# Power_and_Shield_Conn.net
KiCad netlist of a schematic drawn in Altium Designer
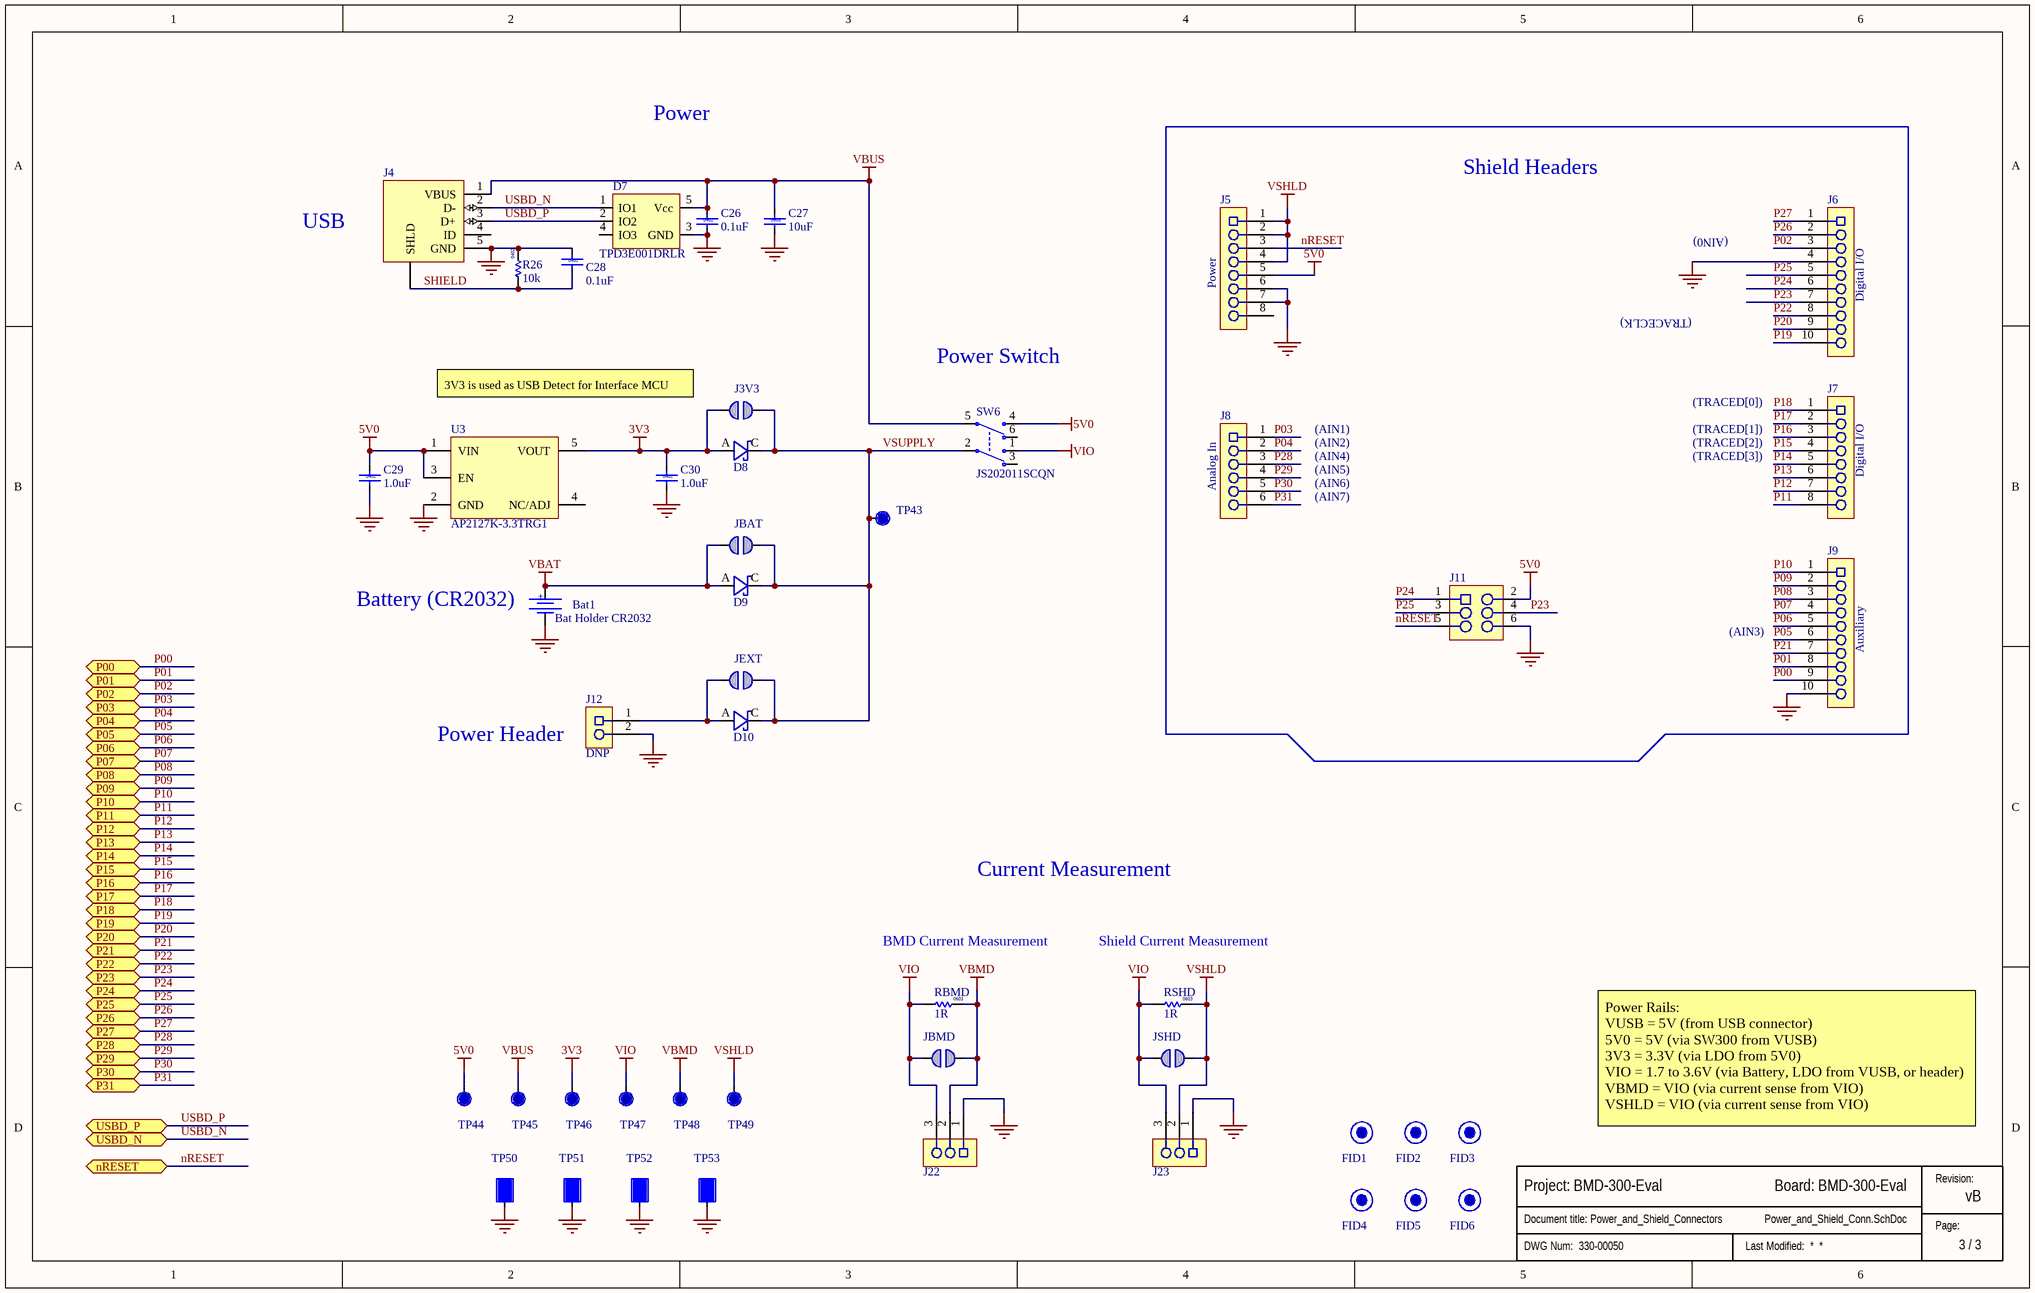
[diagram p0: Power_and_Shield_Conn.SchDoc]

(export (version "E")
  (design (tool "Eeschema 10.0.6"))
  (components
    (comp (ref "Bat1")
      (value "Bat Holder CR2032")
      (footprint "CR2032_HOLDER_SMD")
      (description "Bat Holder CR2032 SMD")
      (fields
        (field (name "MANUFACTURER") "Keystone")
        (field (name "MANUFACTURER PART NUMBER") "3002")
        (field (name "PUBLISHER") "Nordic Semiconductor")
      )
      (libsource (lib "pca10036") (part "Battery"))
    )
    (comp (ref "C26")
      (value "0.1uF")
      (footprint "Cap 0402 HD")
      (description "Cap, Ceramic 0.1uF 10V 10% X5R 0402")
      (fields
        (field (name "SIZE") "0402")
        (field (name "PART NUMBER") "120-00016")
        (field (name "MANUFACTURER") "Murata Electronics North America")
      )
      (libsource (lib "Arena-Altium DB") (part "Cap Chip"))
    )
    (comp (ref "C27")
      (value "10uF")
      (footprint "Cap 0603 HD")
      (description "Cap, Ceramic 10uF 10V 20% X5R 0603")
      (fields
        (field (name "SIZE") "0603")
        (field (name "PART NUMBER") "120-00024")
        (field (name "MANUFACTURER") "Murata Electronics North America")
      )
      (libsource (lib "Arena-Altium DB") (part "Cap Chip"))
    )
    (comp (ref "C28")
      (value "0.1uF")
      (footprint "Cap 0402 HD")
      (description "Cap, Ceramic 0.1uF 10V 10% X5R 0402")
      (fields
        (field (name "SIZE") "0402")
        (field (name "PART NUMBER") "120-00016")
        (field (name "MANUFACTURER") "Murata Electronics North America")
      )
      (libsource (lib "Arena-Altium DB") (part "Cap Chip"))
    )
    (comp (ref "C29")
      (value "1.0uF")
      (footprint "Cap 0402 HD")
      (description "Cap, Ceramic, 1.0uF 10V 10% X5R, 0402")
      (fields
        (field (name "SIZE") "0402")
        (field (name "PART NUMBER") "120-00017")
        (field (name "MANUFACTURER") "Murata Electronics North America")
      )
      (libsource (lib "Arena-Altium DB") (part "Cap Chip"))
    )
    (comp (ref "C30")
      (value "1.0uF")
      (footprint "Cap 0402 HD")
      (description "Cap, Ceramic, 1.0uF 10V 10% X5R, 0402")
      (fields
        (field (name "SIZE") "0402")
        (field (name "PART NUMBER") "120-00017")
        (field (name "MANUFACTURER") "Murata Electronics North America")
      )
      (libsource (lib "Arena-Altium DB") (part "Cap Chip"))
    )
    (comp (ref "D7")
      (value "110-00018")
      (footprint "SOT-553")
      (description "LOW-CAPACITANCE 3-CHANNEL ESD-PROTECTION ARRAY")
      (fields
        (field (name "MANUFACTURER P/N") "TPD3E001DRLR")
        (field (name "MANUFACTURER") "Texas Instruments")
        (field (name "VOLTAGE") "5V")
      )
      (libsource (lib "Arena-Altium DB") (part "TPD3E001"))
    )
    (comp (ref "D8")
      (value "110-00008")
      (footprint "SOD-123")
      (fields (field (name "MANUFACTURER") "Fairchild Semiconductor") (field (name "VOLTAGE") "20V"))
      (libsource (lib "Arena-Altium DB") (part "Diode_Schottky"))
    )
    (comp (ref "D9")
      (value "110-00008")
      (footprint "SOD-123")
      (fields (field (name "MANUFACTURER") "Fairchild Semiconductor") (field (name "VOLTAGE") "20V"))
      (libsource (lib "Arena-Altium DB") (part "Diode_Schottky"))
    )
    (comp (ref "D10")
      (value "110-00008")
      (footprint "SOD-123")
      (fields (field (name "MANUFACTURER") "Fairchild Semiconductor") (field (name "VOLTAGE") "20V"))
      (libsource (lib "Arena-Altium DB") (part "Diode_Schottky"))
    )
    (comp (ref "FID1")
      (value "FID")
      (footprint "FIDUCIAL40")
      (description "Fiducial, 0.040\" inner Dia, 0.075\" outer Dia")
      (fields
        (field (name "PART NUMBER") "FIDUCIAL.04")
        (field (name "ADDED BY") "Jeremy D")
        (field (name "CHECKED BY") "Paul B")
      )
      (libsource (lib "LEGACY_Rigado_AltiumLib") (part "FIDUCIAL"))
    )
    (comp (ref "FID2")
      (value "FID")
      (footprint "FIDUCIAL40")
      (description "Fiducial, 0.040\" inner Dia, 0.075\" outer Dia")
      (fields
        (field (name "PART NUMBER") "FIDUCIAL.04")
        (field (name "ADDED BY") "Jeremy D")
        (field (name "CHECKED BY") "Paul B")
      )
      (libsource (lib "LEGACY_Rigado_AltiumLib") (part "FIDUCIAL"))
    )
    (comp (ref "FID3")
      (value "FID")
      (footprint "FIDUCIAL40")
      (description "Fiducial, 0.040\" inner Dia, 0.075\" outer Dia")
      (fields
        (field (name "PART NUMBER") "FIDUCIAL.04")
        (field (name "ADDED BY") "Jeremy D")
        (field (name "CHECKED BY") "Paul B")
      )
      (libsource (lib "LEGACY_Rigado_AltiumLib") (part "FIDUCIAL"))
    )
    (comp (ref "FID4")
      (value "FID")
      (footprint "FIDUCIAL40")
      (description "Fiducial, 0.040\" inner Dia, 0.075\" outer Dia")
      (fields
        (field (name "PART NUMBER") "FIDUCIAL.04")
        (field (name "ADDED BY") "Jeremy D")
        (field (name "CHECKED BY") "Paul B")
      )
      (libsource (lib "LEGACY_Rigado_AltiumLib") (part "FIDUCIAL"))
    )
    (comp (ref "FID5")
      (value "FID")
      (footprint "FIDUCIAL40")
      (description "Fiducial, 0.040\" inner Dia, 0.075\" outer Dia")
      (fields
        (field (name "PART NUMBER") "FIDUCIAL.04")
        (field (name "ADDED BY") "Jeremy D")
        (field (name "CHECKED BY") "Paul B")
      )
      (libsource (lib "LEGACY_Rigado_AltiumLib") (part "FIDUCIAL"))
    )
    (comp (ref "FID6")
      (value "FID")
      (footprint "FIDUCIAL40")
      (description "Fiducial, 0.040\" inner Dia, 0.075\" outer Dia")
      (fields
        (field (name "PART NUMBER") "FIDUCIAL.04")
        (field (name "ADDED BY") "Jeremy D")
        (field (name "CHECKED BY") "Paul B")
      )
      (libsource (lib "LEGACY_Rigado_AltiumLib") (part "FIDUCIAL"))
    )
    (comp (ref "J3V3")
      (value "Solderbridge-OpenDNP")
      (footprint "Solderbridge-Open")
      (description "Solderbridge-Open")
      (fields (field (name "ADDED BY") "Paul B"))
      (libsource (lib "LEGACY_Rigado_AltiumLib") (part "Solderbridge-Open"))
    )
    (comp (ref "J4")
      (value "130-00008")
      (footprint "USB_Micro_RA_W-2TABS")
      (description "USB Micro B Receptacle, Right Angle, SMT with 2 TH Tabs")
      (fields (field (name "MANUFACTURER") "FCI"))
      (libsource (lib "Arena-Altium DB") (part "USB_W-Shield"))
    )
    (comp (ref "J5")
      (value "130-00102")
      (footprint "SKT-0.1P-SSM-108-L-SV")
      (description "Con Socket Strip 0.1\" 8 Pin 1Row SMD")
      (fields (field (name "MANUFACTURER") "Samtec") (field (name "VOLTAGE") "572VDC"))
      (libsource (lib "") (part "CON-8Pin_1Row_1"))
    )
    (comp (ref "J6")
      (value "130-00101")
      (footprint "SKT-0.1P-SSM-110-L-SV")
      (description "Con Socket Strip 0.1\" 10Pin 1Row SMD")
      (fields (field (name "MANUFACTURER") "Samtec") (field (name "VOLTAGE") "572VDC"))
      (libsource (lib "Arena-Altium DB") (part "CON-10Pin_1Row"))
    )
    (comp (ref "J7")
      (value "130-00102")
      (footprint "SKT-0.1P-SSM-108-L-SV")
      (description "Con Socket Strip 0.1\" 8 Pin 1Row SMD")
      (fields (field (name "MANUFACTURER") "Samtec") (field (name "VOLTAGE") "572VDC"))
      (libsource (lib "Arena-Altium DB") (part "CON-8Pin_1Row"))
    )
    (comp (ref "J8")
      (value "130-00103")
      (footprint "SKT-0.1P-SSM-106-L-SV")
      (description "Con Socket Strip 0.1\" 6Pin 1Row SMD")
      (fields (field (name "MANUFACTURER") "Samtec") (field (name "VOLTAGE") "572VDC"))
      (libsource (lib "Arena-Altium DB") (part "CON-6Pin_1Row"))
    )
    (comp (ref "J9")
      (value "130-00101")
      (footprint "SKT-0.1P-SSM-110-L-SV")
      (description "Con Socket Strip 0.1\" 10Pin 1Row SMD")
      (fields (field (name "MANUFACTURER") "Samtec") (field (name "VOLTAGE") "572VDC"))
      (libsource (lib "Arena-Altium DB") (part "CON-10Pin_1Row"))
    )
    (comp (ref "J11")
      (value "130-00104")
      (footprint "HDR-0.1P-6Pin-3x2-SMT")
      (description "Header 0.1\" 6 Pin 2 Row SMD Black")
      (fields (field (name "MANUFACTURER") "Molex Inc"))
      (libsource (lib "Arena-Altium DB") (part "CON-6Pin_2Row"))
    )
    (comp (ref "J12")
      (value "130-00048DNP")
      (footprint "HDR-0.1P-2PIN-TH")
      (description "Header 0.100\" Pitch, 2 Pin, 2x1, TH.")
      (fields
        (field (name "DNP") "DNP")
        (field (name "PART NUMBER") "130-00048")
        (field (name "MANUFACTURER") "Sullins Connector Solutions")
      )
      (libsource (lib "Arena-Altium DB") (part "CON-2Pin_1Row"))
    )
    (comp (ref "J22")
      (value "130-00105")
      (footprint "HDR-0.1P-3Pin-1Row-SMT")
      (description "Header, 0.100\" Pitch, 3 Pin, Vertical SMT")
      (fields (field (name "MANUFACTURER") "Harwin Inc"))
      (libsource (lib "Arena-Altium DB") (part "CON-3Pin_1Row"))
    )
    (comp (ref "J23")
      (value "130-00105")
      (footprint "HDR-0.1P-3Pin-1Row-SMT")
      (description "Header, 0.100\" Pitch, 3 Pin, Vertical SMT")
      (fields (field (name "MANUFACTURER") "Harwin Inc"))
      (libsource (lib "Arena-Altium DB") (part "CON-3Pin_1Row"))
    )
    (comp (ref "JBAT")
      (value "Solderbridge-OpenDNP")
      (footprint "Solderbridge-Open")
      (description "Solderbridge-Open")
      (fields (field (name "ADDED BY") "Paul B"))
      (libsource (lib "LEGACY_Rigado_AltiumLib") (part "Solderbridge-Open"))
    )
    (comp (ref "JBMD")
      (value "Solderbridge-OpenDNP")
      (footprint "Solderbridge-Open")
      (description "Solderbridge-Open")
      (fields (field (name "ADDED BY") "Paul B"))
      (libsource (lib "LEGACY_Rigado_AltiumLib") (part "Solderbridge-Open"))
    )
    (comp (ref "JEXT")
      (value "Solderbridge-OpenDNP")
      (footprint "Solderbridge-Open")
      (description "Solderbridge-Open")
      (fields (field (name "ADDED BY") "Paul B"))
      (libsource (lib "LEGACY_Rigado_AltiumLib") (part "Solderbridge-Open"))
    )
    (comp (ref "JSHD")
      (value "Solderbridge-OpenDNP")
      (footprint "Solderbridge-Open")
      (description "Solderbridge-Open")
      (fields (field (name "ADDED BY") "Paul B"))
      (libsource (lib "LEGACY_Rigado_AltiumLib") (part "Solderbridge-Open"))
    )
    (comp (ref "R26")
      (value "10k")
      (footprint "RES 0402 HD")
      (description "Resistor 10k ohm 1% 1/16W, 0402")
      (fields
        (field (name "SIZE") "0402")
        (field (name "PART NUMBER") "180-00024")
        (field (name "MANUFACTURER") "Rohm Semiconductor")
      )
      (libsource (lib "Arena-Altium DB") (part "Res sm"))
    )
    (comp (ref "RBMD")
      (value "1R")
      (footprint "RES 0603 HD")
      (description "Resistor 1 ohm 1%, 1/10W, 0603")
      (fields
        (field (name "SIZE") "0603")
        (field (name "PART NUMBER") "180-00109")
        (field (name "MANUFACTURER") "Samsung Electro-Mechanics America, Inc")
      )
      (libsource (lib "Arena-Altium DB") (part "Res sm"))
    )
    (comp (ref "RSHD")
      (value "1R")
      (footprint "RES 0603 HD")
      (description "Resistor 1 ohm 1%, 1/10W, 0603")
      (fields
        (field (name "SIZE") "0603")
        (field (name "PART NUMBER") "180-00109")
        (field (name "MANUFACTURER") "Samsung Electro-Mechanics America, Inc")
      )
      (libsource (lib "Arena-Altium DB") (part "Res sm"))
    )
    (comp (ref "SW6")
      (value "137-00006")
      (footprint "SW_Slide_DPDT_JS202011SCQN")
      (description "SWITCH SLIDE DPDT 300MA 6V SMD")
      (fields
        (field (name "MANUFACTURER P/N") "JS202011SCQN")
        (field (name "MANUFACTURER") "C&K Components")
        (field (name "VOLTAGE") "6V")
      )
      (libsource (lib "Arena-Altium DB") (part "SW_DPDT"))
    )
    (comp (ref "TP43")
      (value "TP")
      (footprint "TP10R")
      (description "Testpoint, Round 1.0mm Dia")
      (fields
        (field (name "PART NUMBER") "TP10R")
        (field (name "ADDED BY") "Jeremy D")
        (field (name "CHECKED BY") "Paul B")
      )
      (libsource (lib "LEGACY_Rigado_AltiumLib") (part "TP_R"))
    )
    (comp (ref "TP44")
      (value "TP")
      (footprint "TP12R")
      (description "Testpoint, Round 1.2mm Dia")
      (fields (field (name "PART NUMBER") "TP12R") (field (name "ADDED BY") "Cam N"))
      (libsource (lib "LEGACY_Rigado_AltiumLib") (part "TP_R"))
    )
    (comp (ref "TP45")
      (value "TP")
      (footprint "TP12R")
      (description "Testpoint, Round 1.2mm Dia")
      (fields (field (name "PART NUMBER") "TP12R") (field (name "ADDED BY") "Cam N"))
      (libsource (lib "LEGACY_Rigado_AltiumLib") (part "TP_R"))
    )
    (comp (ref "TP46")
      (value "TP")
      (footprint "TP12R")
      (description "Testpoint, Round 1.2mm Dia")
      (fields (field (name "PART NUMBER") "TP12R") (field (name "ADDED BY") "Cam N"))
      (libsource (lib "LEGACY_Rigado_AltiumLib") (part "TP_R"))
    )
    (comp (ref "TP47")
      (value "TP")
      (footprint "TP12R")
      (description "Testpoint, Round 1.2mm Dia")
      (fields (field (name "PART NUMBER") "TP12R") (field (name "ADDED BY") "Cam N"))
      (libsource (lib "LEGACY_Rigado_AltiumLib") (part "TP_R"))
    )
    (comp (ref "TP48")
      (value "TP")
      (footprint "TP12R")
      (description "Testpoint, Round 1.2mm Dia")
      (fields (field (name "PART NUMBER") "TP12R") (field (name "ADDED BY") "Cam N"))
      (libsource (lib "LEGACY_Rigado_AltiumLib") (part "TP_R"))
    )
    (comp (ref "TP49")
      (value "TP")
      (footprint "TP12R")
      (description "Testpoint, Round 1.2mm Dia")
      (fields (field (name "PART NUMBER") "TP12R") (field (name "ADDED BY") "Cam N"))
      (libsource (lib "LEGACY_Rigado_AltiumLib") (part "TP_R"))
    )
    (comp (ref "TP50")
      (value "TP4.5x3SqDNP")
      (footprint "TP4.5x3Sq")
      (description "Testpoint, Rectangular 4.5mm x 3mm")
      (fields (field (name "PART NUMBER") "TP4.5x3Sq") (field (name "ADDED BY") "Jeremy D"))
      (libsource (lib "LEGACY_Rigado_AltiumLib") (part "TP_Sq"))
    )
    (comp (ref "TP51")
      (value "TP4.5x3SqDNP")
      (footprint "TP4.5x3Sq")
      (description "Testpoint, Rectangular 4.5mm x 3mm")
      (fields (field (name "PART NUMBER") "TP4.5x3Sq") (field (name "ADDED BY") "Jeremy D"))
      (libsource (lib "LEGACY_Rigado_AltiumLib") (part "TP_Sq"))
    )
    (comp (ref "TP52")
      (value "TP4.5x3SqDNP")
      (footprint "TP4.5x3Sq")
      (description "Testpoint, Rectangular 4.5mm x 3mm")
      (fields (field (name "PART NUMBER") "TP4.5x3Sq") (field (name "ADDED BY") "Jeremy D"))
      (libsource (lib "LEGACY_Rigado_AltiumLib") (part "TP_Sq"))
    )
    (comp (ref "TP53")
      (value "TP4.5x3SqDNP")
      (footprint "TP4.5x3Sq")
      (description "Testpoint, Rectangular 4.5mm x 3mm")
      (fields (field (name "PART NUMBER") "TP4.5x3Sq") (field (name "ADDED BY") "Jeremy D"))
      (libsource (lib "LEGACY_Rigado_AltiumLib") (part "TP_Sq"))
    )
    (comp (ref "U3")
      (value "260-00024")
      (footprint "SOT-23-5")
      (description "IC REG LDO 3.3V 0.3A SOT23-5")
      (fields
        (field (name "MANUFACTURER P/N") "AP2127K-3.3TRG1")
        (field (name "MANUFACTURER") "Diodes Incorporated")
        (field (name "VOLTAGE") "6V")
      )
      (libsource (lib "Arena-Altium DB") (part "LDO_5Pin_ALT"))
    )
  )
  (nets
    (net (code "1") (name "/P00") (class "Default") (node (ref "J9") (pin "9") (pintype "passive")))
    (net (code "2") (name "/P01") (class "Default") (node (ref "J9") (pin "8") (pintype "passive")))
    (net (code "3") (name "/P02") (class "Default") (node (ref "J6") (pin "3") (pintype "passive")))
    (net (code "4") (name "/P03") (class "Default")
      (node (ref "J8") (pin "1") (pinfunction "1_1") (pintype "passive"))
    )
    (net (code "5") (name "/P04") (class "Default")
      (node (ref "J8") (pin "2") (pinfunction "2_2") (pintype "passive"))
    )
    (net (code "6") (name "/P05") (class "Default") (node (ref "J9") (pin "6") (pintype "passive")))
    (net (code "7") (name "/P06") (class "Default") (node (ref "J9") (pin "5") (pintype "passive")))
    (net (code "8") (name "/P07") (class "Default") (node (ref "J9") (pin "4") (pintype "passive")))
    (net (code "9") (name "/P08") (class "Default") (node (ref "J9") (pin "3") (pintype "passive")))
    (net (code "10") (name "/P09") (class "Default") (node (ref "J9") (pin "2") (pintype "passive")))
    (net (code "11") (name "/P10") (class "Default") (node (ref "J9") (pin "1") (pintype "passive")))
    (net (code "12") (name "/P11") (class "Default") (node (ref "J7") (pin "8") (pintype "passive")))
    (net (code "13") (name "/P12") (class "Default") (node (ref "J7") (pin "7") (pintype "passive")))
    (net (code "14") (name "/P13") (class "Default") (node (ref "J7") (pin "6") (pintype "passive")))
    (net (code "15") (name "/P14") (class "Default") (node (ref "J7") (pin "5") (pintype "passive")))
    (net (code "16") (name "/P15") (class "Default") (node (ref "J7") (pin "4") (pintype "passive")))
    (net (code "17") (name "/P16") (class "Default") (node (ref "J7") (pin "3") (pintype "passive")))
    (net (code "18") (name "/P17") (class "Default") (node (ref "J7") (pin "2") (pintype "passive")))
    (net (code "19") (name "/P18") (class "Default") (node (ref "J7") (pin "1") (pintype "passive")))
    (net (code "20") (name "/P19") (class "Default") (node (ref "J6") (pin "10") (pintype "passive")))
    (net (code "21") (name "/P20") (class "Default") (node (ref "J6") (pin "9") (pintype "passive")))
    (net (code "22") (name "/P21") (class "Default") (node (ref "J9") (pin "7") (pintype "passive")))
    (net (code "23") (name "/P22") (class "Default") (node (ref "J6") (pin "8") (pintype "passive")))
    (net (code "24") (name "/P23") (class "Default")
      (node (ref "J11") (pin "4") (pintype "passive"))
      (node (ref "J6") (pin "7") (pintype "passive"))
    )
    (net (code "25") (name "/P24") (class "Default")
      (node (ref "J11") (pin "1") (pintype "passive"))
      (node (ref "J6") (pin "6") (pintype "passive"))
    )
    (net (code "26") (name "/P25") (class "Default")
      (node (ref "J11") (pin "3") (pintype "passive"))
      (node (ref "J6") (pin "5") (pintype "passive"))
    )
    (net (code "27") (name "/P26") (class "Default") (node (ref "J6") (pin "2") (pintype "passive")))
    (net (code "28") (name "/P27") (class "Default") (node (ref "J6") (pin "1") (pintype "passive")))
    (net (code "29") (name "/P28") (class "Default")
      (node (ref "J8") (pin "3") (pinfunction "3_3") (pintype "passive"))
    )
    (net (code "30") (name "/P29") (class "Default")
      (node (ref "J8") (pin "4") (pinfunction "4_4") (pintype "passive"))
    )
    (net (code "31") (name "/P30") (class "Default")
      (node (ref "J8") (pin "5") (pinfunction "5_5") (pintype "passive"))
    )
    (net (code "32") (name "/P31") (class "Default")
      (node (ref "J8") (pin "6") (pinfunction "6_6") (pintype "passive"))
    )
    (net (code "33") (name "/SHIELD") (class "Default")
      (node (ref "C28") (pin "2") (pinfunction "2_2") (pintype "passive"))
      (node (ref "J4") (pin "6") (pinfunction "SHLD_6") (pintype "passive"))
      (node (ref "R26") (pin "1") (pinfunction "1_1") (pintype "passive"))
    )
    (net (code "34") (name "/USBD_N") (class "Default")
      (node (ref "D7") (pin "1") (pinfunction "IO1_1") (pintype "passive"))
      (node (ref "J4") (pin "2") (pinfunction "D-_2") (pintype "bidirectional"))
    )
    (net (code "35") (name "/USBD_P") (class "Default")
      (node (ref "D7") (pin "2") (pinfunction "IO2_2") (pintype "passive"))
      (node (ref "J4") (pin "3") (pinfunction "D+_3") (pintype "bidirectional"))
    )
    (net (code "36") (name "/VSUPPLY") (class "Default")
      (node (ref "D10") (pin "C") (pinfunction "Cathode_C") (pintype "passive"))
      (node (ref "D8") (pin "C") (pinfunction "Cathode_C") (pintype "passive"))
      (node (ref "D9") (pin "C") (pinfunction "Cathode_C") (pintype "passive"))
      (node (ref "J3V3") (pin "1") (pinfunction "1_1") (pintype "passive"))
      (node (ref "JBAT") (pin "1") (pinfunction "1_1") (pintype "passive"))
      (node (ref "JEXT") (pin "1") (pinfunction "1_1") (pintype "passive"))
      (node (ref "SW6") (pin "2") (pinfunction "COM-1_2") (pintype "passive"))
      (node (ref "TP43") (pin "1") (pintype "passive"))
    )
    (net (code "37") (name "/nRESET") (class "Default")
      (node (ref "J11") (pin "5") (pintype "passive"))
      (node (ref "J5") (pin "3") (pintype "passive"))
    )
    (net (code "38") (name "3V3") (class "Default")
      (node (ref "C30") (pin "1") (pinfunction "1_1") (pintype "passive"))
      (node (ref "D8") (pin "A") (pinfunction "Anode_A") (pintype "passive"))
      (node (ref "J3V3") (pin "2") (pinfunction "2_2") (pintype "passive"))
      (node (ref "TP46") (pin "1") (pintype "passive"))
      (node (ref "U3") (pin "5") (pinfunction "VOUT_5") (pintype "power_in"))
    )
    (net (code "39") (name "5V0") (class "Default")
      (node (ref "C29") (pin "1") (pinfunction "1_1") (pintype "passive"))
      (node (ref "J11") (pin "2") (pintype "passive"))
      (node (ref "J5") (pin "5") (pintype "passive"))
      (node (ref "SW6") (pin "4") (pinfunction "N.O-2_4") (pintype "passive"))
      (node (ref "TP44") (pin "1") (pintype "passive"))
      (node (ref "U3") (pin "1") (pinfunction "VIN_1") (pintype "power_in"))
      (node (ref "U3") (pin "3") (pinfunction "EN_3") (pintype "passive"))
    )
    (net (code "40") (name "GND") (class "Default")
      (node (ref "Bat1") (pin "2") (pintype "passive"))
      (node (ref "C26") (pin "2") (pinfunction "2_2") (pintype "passive"))
      (node (ref "C27") (pin "2") (pinfunction "2_2") (pintype "passive"))
      (node (ref "C28") (pin "1") (pinfunction "1_1") (pintype "passive"))
      (node (ref "C29") (pin "2") (pinfunction "2_2") (pintype "passive"))
      (node (ref "C30") (pin "2") (pinfunction "2_2") (pintype "passive"))
      (node (ref "D7") (pin "3") (pinfunction "GND_3") (pintype "power_in"))
      (node (ref "J11") (pin "6") (pintype "passive"))
      (node (ref "J12") (pin "2") (pinfunction "2_2") (pintype "passive"))
      (node (ref "J22") (pin "1") (pinfunction "1_1") (pintype "passive"))
      (node (ref "J23") (pin "1") (pinfunction "1_1") (pintype "passive"))
      (node (ref "J4") (pin "5") (pinfunction "GND_5") (pintype "power_in"))
      (node (ref "J5") (pin "6") (pintype "passive"))
      (node (ref "J5") (pin "7") (pintype "passive"))
      (node (ref "J6") (pin "4") (pintype "passive"))
      (node (ref "J9") (pin "10") (pintype "passive"))
      (node (ref "R26") (pin "2") (pinfunction "2_2") (pintype "passive"))
      (node (ref "TP50") (pin "1") (pintype "passive"))
      (node (ref "TP51") (pin "1") (pintype "passive"))
      (node (ref "TP52") (pin "1") (pintype "passive"))
      (node (ref "TP53") (pin "1") (pintype "passive"))
      (node (ref "U3") (pin "2") (pinfunction "GND_2") (pintype "power_in"))
    )
    (net (code "41") (name "Net-(D10-Anode)") (class "Default")
      (node (ref "D10") (pin "A") (pinfunction "Anode_A") (pintype "passive"))
      (node (ref "J12") (pin "1") (pinfunction "1_1") (pintype "passive"))
      (node (ref "JEXT") (pin "2") (pinfunction "2_2") (pintype "passive"))
    )
    (net (code "42") (name "VBAT") (class "Default")
      (node (ref "Bat1") (pin "1") (pintype "passive"))
      (node (ref "D9") (pin "A") (pinfunction "Anode_A") (pintype "passive"))
      (node (ref "JBAT") (pin "2") (pinfunction "2_2") (pintype "passive"))
    )
    (net (code "43") (name "VBMD") (class "Default")
      (node (ref "J22") (pin "2") (pinfunction "2_2") (pintype "passive"))
      (node (ref "JBMD") (pin "1") (pinfunction "1_1") (pintype "passive"))
      (node (ref "RBMD") (pin "2") (pinfunction "2_2") (pintype "passive"))
      (node (ref "TP48") (pin "1") (pintype "passive"))
    )
    (net (code "44") (name "VBUS") (class "Default")
      (node (ref "C26") (pin "1") (pinfunction "1_1") (pintype "passive"))
      (node (ref "C27") (pin "1") (pinfunction "1_1") (pintype "passive"))
      (node (ref "D7") (pin "5") (pinfunction "Vcc_5") (pintype "power_in"))
      (node (ref "J4") (pin "1") (pinfunction "VBUS_1") (pintype "power_in"))
      (node (ref "SW6") (pin "5") (pinfunction "COM-2_5") (pintype "passive"))
      (node (ref "TP45") (pin "1") (pintype "passive"))
    )
    (net (code "45") (name "VIO") (class "Default")
      (node (ref "J22") (pin "3") (pinfunction "3_3") (pintype "passive"))
      (node (ref "J23") (pin "3") (pinfunction "3_3") (pintype "passive"))
      (node (ref "JBMD") (pin "2") (pinfunction "2_2") (pintype "passive"))
      (node (ref "JSHD") (pin "2") (pinfunction "2_2") (pintype "passive"))
      (node (ref "RBMD") (pin "1") (pinfunction "1_1") (pintype "passive"))
      (node (ref "RSHD") (pin "1") (pinfunction "1_1") (pintype "passive"))
      (node (ref "SW6") (pin "1") (pinfunction "N.O-1_1") (pintype "passive"))
      (node (ref "TP47") (pin "1") (pintype "passive"))
    )
    (net (code "46") (name "VSHLD") (class "Default")
      (node (ref "J23") (pin "2") (pinfunction "2_2") (pintype "passive"))
      (node (ref "J5") (pin "1") (pintype "passive"))
      (node (ref "J5") (pin "2") (pintype "passive"))
      (node (ref "J5") (pin "4") (pintype "passive"))
      (node (ref "JSHD") (pin "1") (pinfunction "1_1") (pintype "passive"))
      (node (ref "RSHD") (pin "2") (pinfunction "2_2") (pintype "passive"))
      (node (ref "TP49") (pin "1") (pintype "passive"))
    )
    (net (code "47") (name "unconnected-(D7-IO3-Pad4)") (class "Default")
      (node (ref "D7") (pin "4") (pinfunction "IO3_4") (pintype "passive"))
    )
    (net (code "48") (name "unconnected-(J4-ID-Pad4)") (class "Default")
      (node (ref "J4") (pin "4") (pinfunction "ID_4") (pintype "passive"))
    )
    (net (code "49") (name "unconnected-(J5-Pad8)") (class "Default")
      (node (ref "J5") (pin "8") (pintype "passive"))
    )
    (net (code "50") (name "unconnected-(SW6-N.C-1-Pad3)") (class "Default")
      (node (ref "SW6") (pin "3") (pinfunction "N.C-1_3") (pintype "passive"))
    )
    (net (code "51") (name "unconnected-(SW6-N.C-2-Pad6)") (class "Default")
      (node (ref "SW6") (pin "6") (pinfunction "N.C-2_6") (pintype "passive"))
    )
    (net (code "52") (name "unconnected-(U3-NC{slash}ADJ-Pad4)") (class "Default")
      (node (ref "U3") (pin "4") (pinfunction "NC/ADJ_4") (pintype "passive"))
    )
  )
)
